# PCB-CMB-5-SKAARDUINO.net
KiCad netlist of a schematic drawn in EAGLE
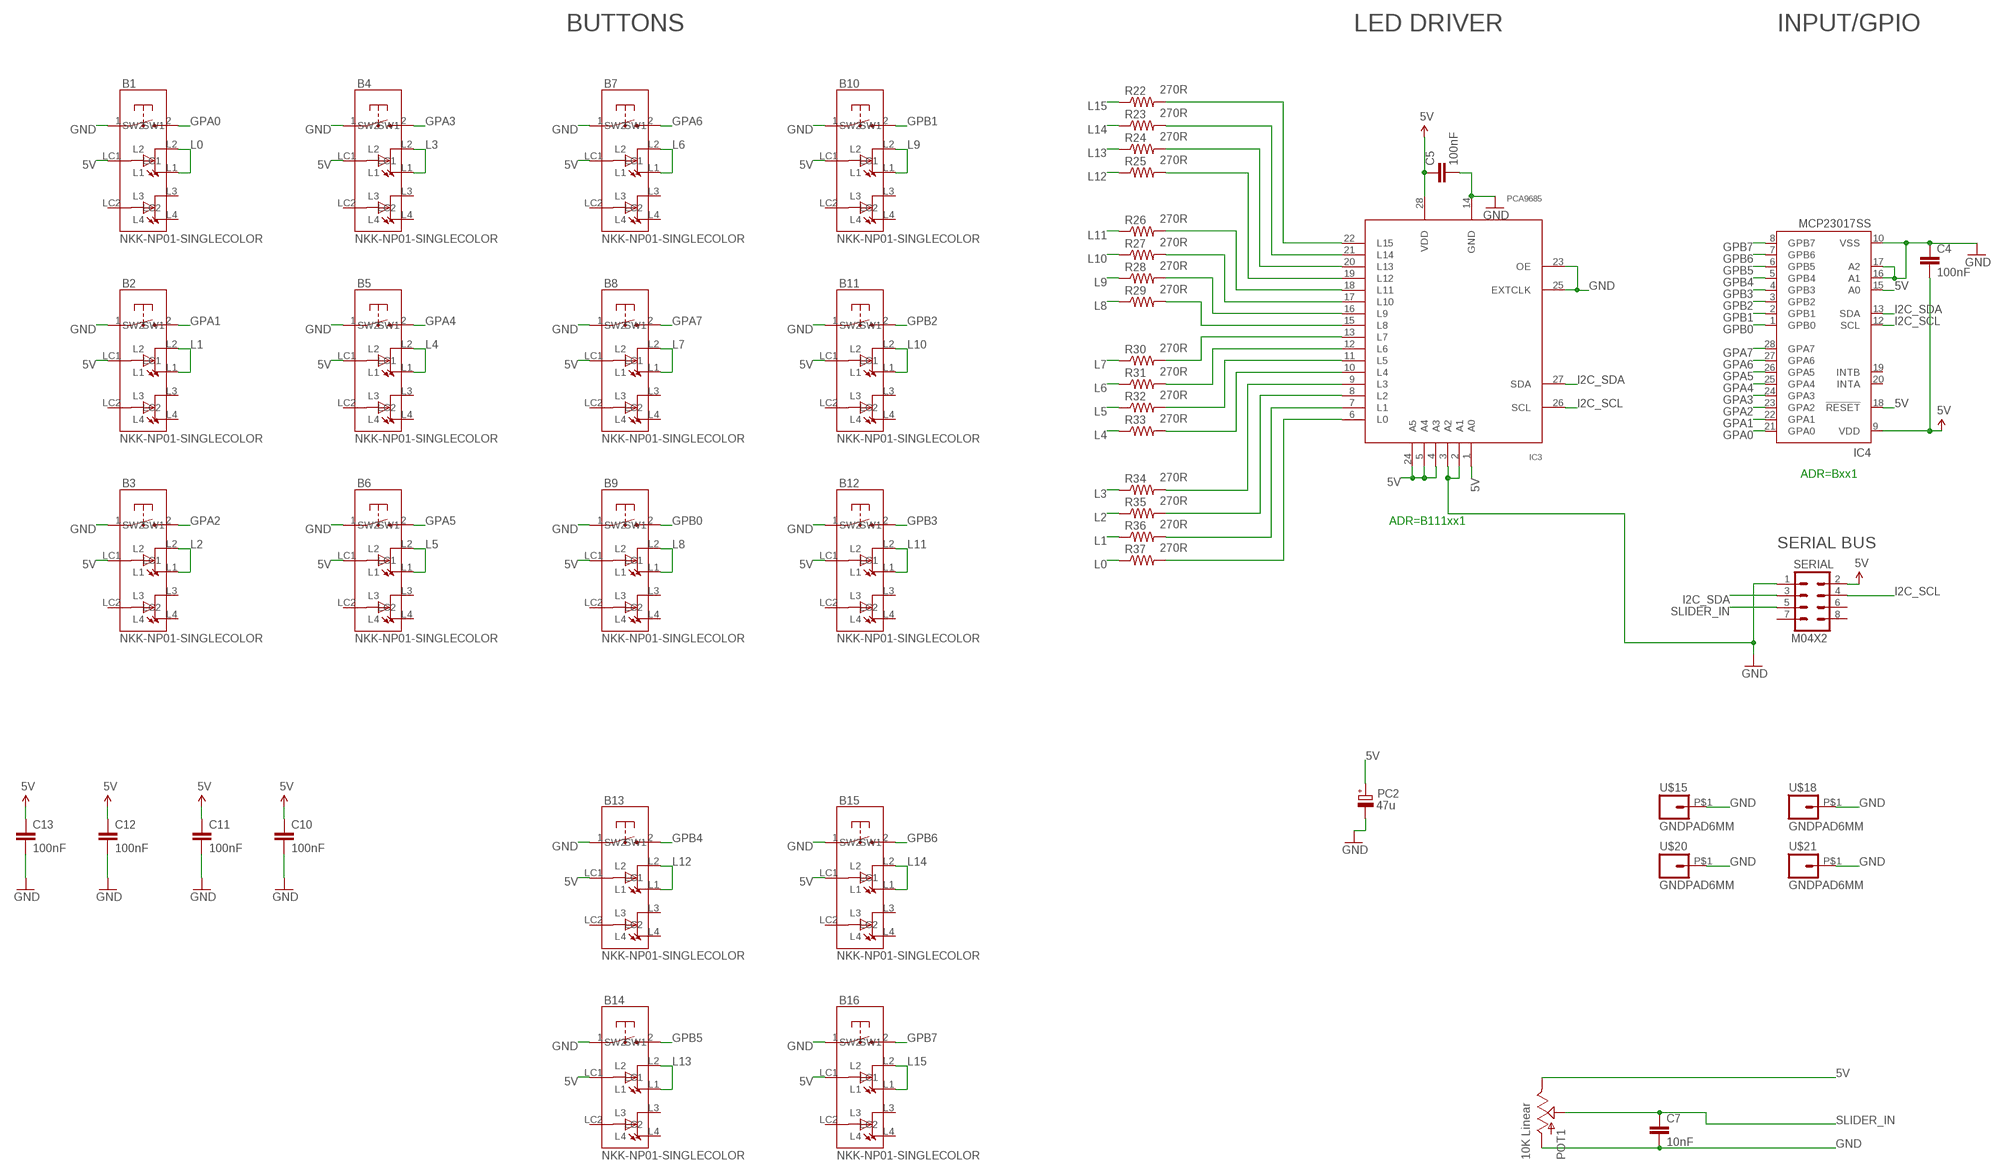
[diagram p0: schematic, sheet 1]

(export (version "E")
  (design (tool "Eeschema 10.0.6"))
  (components
    (comp (ref "B1")
      (value "NKK-NP01-SINGLECOLOR")
      (footprint "eagle-import:NKK-NP01")
      (libsource (lib "eagle-import") (part "NKK-NP01-SINGLECOLOR"))
    )
    (comp (ref "B2")
      (value "NKK-NP01-SINGLECOLOR")
      (footprint "eagle-import:NKK-NP01")
      (libsource (lib "eagle-import") (part "NKK-NP01-SINGLECOLOR"))
    )
    (comp (ref "B3")
      (value "NKK-NP01-SINGLECOLOR")
      (footprint "eagle-import:NKK-NP01")
      (libsource (lib "eagle-import") (part "NKK-NP01-SINGLECOLOR"))
    )
    (comp (ref "B4")
      (value "NKK-NP01-SINGLECOLOR")
      (footprint "eagle-import:NKK-NP01")
      (libsource (lib "eagle-import") (part "NKK-NP01-SINGLECOLOR"))
    )
    (comp (ref "B5")
      (value "NKK-NP01-SINGLECOLOR")
      (footprint "eagle-import:NKK-NP01")
      (libsource (lib "eagle-import") (part "NKK-NP01-SINGLECOLOR"))
    )
    (comp (ref "B6")
      (value "NKK-NP01-SINGLECOLOR")
      (footprint "eagle-import:NKK-NP01")
      (libsource (lib "eagle-import") (part "NKK-NP01-SINGLECOLOR"))
    )
    (comp (ref "B7")
      (value "NKK-NP01-SINGLECOLOR")
      (footprint "eagle-import:NKK-NP01")
      (libsource (lib "eagle-import") (part "NKK-NP01-SINGLECOLOR"))
    )
    (comp (ref "B8")
      (value "NKK-NP01-SINGLECOLOR")
      (footprint "eagle-import:NKK-NP01")
      (libsource (lib "eagle-import") (part "NKK-NP01-SINGLECOLOR"))
    )
    (comp (ref "B9")
      (value "NKK-NP01-SINGLECOLOR")
      (footprint "eagle-import:NKK-NP01")
      (libsource (lib "eagle-import") (part "NKK-NP01-SINGLECOLOR"))
    )
    (comp (ref "B10")
      (value "NKK-NP01-SINGLECOLOR")
      (footprint "eagle-import:NKK-NP01")
      (libsource (lib "eagle-import") (part "NKK-NP01-SINGLECOLOR"))
    )
    (comp (ref "B11")
      (value "NKK-NP01-SINGLECOLOR")
      (footprint "eagle-import:NKK-NP01")
      (libsource (lib "eagle-import") (part "NKK-NP01-SINGLECOLOR"))
    )
    (comp (ref "B12")
      (value "NKK-NP01-SINGLECOLOR")
      (footprint "eagle-import:NKK-NP01")
      (libsource (lib "eagle-import") (part "NKK-NP01-SINGLECOLOR"))
    )
    (comp (ref "B13")
      (value "NKK-NP01-SINGLECOLOR")
      (footprint "eagle-import:NKK-NP01")
      (libsource (lib "eagle-import") (part "NKK-NP01-SINGLECOLOR"))
    )
    (comp (ref "B14")
      (value "NKK-NP01-SINGLECOLOR")
      (footprint "eagle-import:NKK-NP01")
      (libsource (lib "eagle-import") (part "NKK-NP01-SINGLECOLOR"))
    )
    (comp (ref "B15")
      (value "NKK-NP01-SINGLECOLOR")
      (footprint "eagle-import:NKK-NP01")
      (libsource (lib "eagle-import") (part "NKK-NP01-SINGLECOLOR"))
    )
    (comp (ref "B16")
      (value "NKK-NP01-SINGLECOLOR")
      (footprint "eagle-import:NKK-NP01")
      (libsource (lib "eagle-import") (part "NKK-NP01-SINGLECOLOR"))
    )
    (comp (ref "C4")
      (value "100nF")
      (footprint "eagle-import:0603-CAP")
      (libsource (lib "eagle-import") (part "CAP0603-CAP"))
    )
    (comp (ref "C5")
      (value "100nF")
      (footprint "eagle-import:0603-CAP")
      (libsource (lib "eagle-import") (part "CAP0603-CAP"))
    )
    (comp (ref "C7")
      (value "10nF")
      (footprint "eagle-import:0603-CAP")
      (libsource (lib "eagle-import") (part "CAP0603-CAP"))
    )
    (comp (ref "C10")
      (value "100nF")
      (footprint "eagle-import:0603-CAP")
      (libsource (lib "eagle-import") (part "CAP0603-CAP"))
    )
    (comp (ref "C11")
      (value "100nF")
      (footprint "eagle-import:0603-CAP")
      (libsource (lib "eagle-import") (part "CAP0603-CAP"))
    )
    (comp (ref "C12")
      (value "100nF")
      (footprint "eagle-import:0603-CAP")
      (libsource (lib "eagle-import") (part "CAP0603-CAP"))
    )
    (comp (ref "C13")
      (value "100nF")
      (footprint "eagle-import:0603-CAP")
      (libsource (lib "eagle-import") (part "CAP0603-CAP"))
    )
    (comp (ref "IC3")
      (value "PCA9685")
      (footprint "eagle-import:TSSOP28")
      (libsource (lib "eagle-import") (part "PCA9685"))
    )
    (comp (ref "IC4")
      (value "MCP23017SS")
      (footprint "eagle-import:SSOP28")
      (fields
        (field (name "MF") "MICROCHIP")
        (field (name "MPN") "MCP23017-E/SS")
        (field (name "MPN_1") "MCP23017-E/SS")
        (field (name "OC_FARNELL") "1467674")
        (field (name "OC_NEWARK") "31K2960")
      )
      (libsource (lib "eagle-import") (part "MCP23017SS"))
    )
    (comp (ref "PC2")
      (value "47u")
      (footprint "eagle-import:PANASONIC_D")
      (libsource (lib "eagle-import") (part "CPOL-EUD"))
    )
    (comp (ref "POT1")
      (value "10K Linear")
      (footprint "eagle-import:SLIDER20")
      (libsource (lib "eagle-import") (part "SLIDER20"))
    )
    (comp (ref "R22")
      (value "270R")
      (footprint "eagle-import:0603-RES")
      (libsource (lib "eagle-import") (part "RESISTOR0603-RES"))
    )
    (comp (ref "R23")
      (value "270R")
      (footprint "eagle-import:0603-RES")
      (libsource (lib "eagle-import") (part "RESISTOR0603-RES"))
    )
    (comp (ref "R24")
      (value "270R")
      (footprint "eagle-import:0603-RES")
      (libsource (lib "eagle-import") (part "RESISTOR0603-RES"))
    )
    (comp (ref "R25")
      (value "270R")
      (footprint "eagle-import:0603-RES")
      (libsource (lib "eagle-import") (part "RESISTOR0603-RES"))
    )
    (comp (ref "R26")
      (value "270R")
      (footprint "eagle-import:0603-RES")
      (libsource (lib "eagle-import") (part "RESISTOR0603-RES"))
    )
    (comp (ref "R27")
      (value "270R")
      (footprint "eagle-import:0603-RES")
      (libsource (lib "eagle-import") (part "RESISTOR0603-RES"))
    )
    (comp (ref "R28")
      (value "270R")
      (footprint "eagle-import:0603-RES")
      (libsource (lib "eagle-import") (part "RESISTOR0603-RES"))
    )
    (comp (ref "R29")
      (value "270R")
      (footprint "eagle-import:0603-RES")
      (libsource (lib "eagle-import") (part "RESISTOR0603-RES"))
    )
    (comp (ref "R30")
      (value "270R")
      (footprint "eagle-import:0603-RES")
      (libsource (lib "eagle-import") (part "RESISTOR0603-RES"))
    )
    (comp (ref "R31")
      (value "270R")
      (footprint "eagle-import:0603-RES")
      (libsource (lib "eagle-import") (part "RESISTOR0603-RES"))
    )
    (comp (ref "R32")
      (value "270R")
      (footprint "eagle-import:0603-RES")
      (libsource (lib "eagle-import") (part "RESISTOR0603-RES"))
    )
    (comp (ref "R33")
      (value "270R")
      (footprint "eagle-import:0603-RES")
      (libsource (lib "eagle-import") (part "RESISTOR0603-RES"))
    )
    (comp (ref "R34")
      (value "270R")
      (footprint "eagle-import:0603-RES")
      (libsource (lib "eagle-import") (part "RESISTOR0603-RES"))
    )
    (comp (ref "R35")
      (value "270R")
      (footprint "eagle-import:0603-RES")
      (libsource (lib "eagle-import") (part "RESISTOR0603-RES"))
    )
    (comp (ref "R36")
      (value "270R")
      (footprint "eagle-import:0603-RES")
      (libsource (lib "eagle-import") (part "RESISTOR0603-RES"))
    )
    (comp (ref "R37")
      (value "270R")
      (footprint "eagle-import:0603-RES")
      (libsource (lib "eagle-import") (part "RESISTOR0603-RES"))
    )
    (comp (ref "SERIAL")
      (value "M04X2")
      (footprint "eagle-import:2X4")
      (libsource (lib "eagle-import") (part "M04X2"))
    )
    (comp (ref "U$15")
      (value "GNDPAD6MM")
      (footprint "eagle-import:3.2MMPAD6MM")
      (libsource (lib "eagle-import") (part "GNDPAD6MM"))
    )
    (comp (ref "U$18")
      (value "GNDPAD6MM")
      (footprint "eagle-import:3.2MMPAD6MM")
      (libsource (lib "eagle-import") (part "GNDPAD6MM"))
    )
    (comp (ref "U$20")
      (value "GNDPAD6MM")
      (footprint "eagle-import:3.2MMPAD6MM")
      (libsource (lib "eagle-import") (part "GNDPAD6MM"))
    )
    (comp (ref "U$21")
      (value "GNDPAD6MM")
      (footprint "eagle-import:3.2MMPAD6MM")
      (libsource (lib "eagle-import") (part "GNDPAD6MM"))
    )
  )
  (nets
    (net (code "1") (name "5V") (class "Default")
      (node (ref "B1") (pin "LC1") (pinfunction "LC1_LC1") (pintype "bidirectional"))
      (node (ref "B10") (pin "LC1") (pinfunction "LC1_LC1") (pintype "bidirectional"))
      (node (ref "B11") (pin "LC1") (pinfunction "LC1_LC1") (pintype "bidirectional"))
      (node (ref "B12") (pin "LC1") (pinfunction "LC1_LC1") (pintype "bidirectional"))
      (node (ref "B13") (pin "LC1") (pinfunction "LC1_LC1") (pintype "bidirectional"))
      (node (ref "B14") (pin "LC1") (pinfunction "LC1_LC1") (pintype "bidirectional"))
      (node (ref "B15") (pin "LC1") (pinfunction "LC1_LC1") (pintype "bidirectional"))
      (node (ref "B16") (pin "LC1") (pinfunction "LC1_LC1") (pintype "bidirectional"))
      (node (ref "B2") (pin "LC1") (pinfunction "LC1_LC1") (pintype "bidirectional"))
      (node (ref "B3") (pin "LC1") (pinfunction "LC1_LC1") (pintype "bidirectional"))
      (node (ref "B4") (pin "LC1") (pinfunction "LC1_LC1") (pintype "bidirectional"))
      (node (ref "B5") (pin "LC1") (pinfunction "LC1_LC1") (pintype "bidirectional"))
      (node (ref "B6") (pin "LC1") (pinfunction "LC1_LC1") (pintype "bidirectional"))
      (node (ref "B7") (pin "LC1") (pinfunction "LC1_LC1") (pintype "bidirectional"))
      (node (ref "B8") (pin "LC1") (pinfunction "LC1_LC1") (pintype "bidirectional"))
      (node (ref "B9") (pin "LC1") (pinfunction "LC1_LC1") (pintype "bidirectional"))
      (node (ref "C10") (pin "1") (pinfunction "1_1") (pintype "passive"))
      (node (ref "C11") (pin "1") (pinfunction "1_1") (pintype "passive"))
      (node (ref "C12") (pin "1") (pinfunction "1_1") (pintype "passive"))
      (node (ref "C13") (pin "1") (pinfunction "1_1") (pintype "passive"))
      (node (ref "C4") (pin "2") (pinfunction "2_2") (pintype "passive"))
      (node (ref "C5") (pin "1") (pinfunction "1_1") (pintype "passive"))
      (node (ref "IC3") (pin "1") (pinfunction "A0_1") (pintype "input"))
      (node (ref "IC3") (pin "24") (pinfunction "A5_24") (pintype "input"))
      (node (ref "IC3") (pin "28") (pinfunction "VDD_28") (pintype "power_in"))
      (node (ref "IC3") (pin "4") (pinfunction "A3_4") (pintype "input"))
      (node (ref "IC3") (pin "5") (pinfunction "A4_5") (pintype "input"))
      (node (ref "IC4") (pin "15") (pinfunction "A0_15") (pintype "input"))
      (node (ref "IC4") (pin "18") (pinfunction "~{RESET}_18") (pintype "input"))
      (node (ref "IC4") (pin "9") (pinfunction "VDD_9") (pintype "power_in"))
      (node (ref "PC2") (pin "+") (pinfunction "+_+") (pintype "passive"))
      (node (ref "POT1") (pin "1") (pinfunction "E_1") (pintype "passive"))
      (node (ref "SERIAL") (pin "2") (pinfunction "2_2") (pintype "passive"))
    )
    (net (code "2") (name "GND") (class "Default")
      (node (ref "B1") (pin "1") (pinfunction "SW1_1") (pintype "bidirectional"))
      (node (ref "B10") (pin "1") (pinfunction "SW1_1") (pintype "bidirectional"))
      (node (ref "B11") (pin "1") (pinfunction "SW1_1") (pintype "bidirectional"))
      (node (ref "B12") (pin "1") (pinfunction "SW1_1") (pintype "bidirectional"))
      (node (ref "B13") (pin "1") (pinfunction "SW1_1") (pintype "bidirectional"))
      (node (ref "B14") (pin "1") (pinfunction "SW1_1") (pintype "bidirectional"))
      (node (ref "B15") (pin "1") (pinfunction "SW1_1") (pintype "bidirectional"))
      (node (ref "B16") (pin "1") (pinfunction "SW1_1") (pintype "bidirectional"))
      (node (ref "B2") (pin "1") (pinfunction "SW1_1") (pintype "bidirectional"))
      (node (ref "B3") (pin "1") (pinfunction "SW1_1") (pintype "bidirectional"))
      (node (ref "B4") (pin "1") (pinfunction "SW1_1") (pintype "bidirectional"))
      (node (ref "B5") (pin "1") (pinfunction "SW1_1") (pintype "bidirectional"))
      (node (ref "B6") (pin "1") (pinfunction "SW1_1") (pintype "bidirectional"))
      (node (ref "B7") (pin "1") (pinfunction "SW1_1") (pintype "bidirectional"))
      (node (ref "B8") (pin "1") (pinfunction "SW1_1") (pintype "bidirectional"))
      (node (ref "B9") (pin "1") (pinfunction "SW1_1") (pintype "bidirectional"))
      (node (ref "C10") (pin "2") (pinfunction "2_2") (pintype "passive"))
      (node (ref "C11") (pin "2") (pinfunction "2_2") (pintype "passive"))
      (node (ref "C12") (pin "2") (pinfunction "2_2") (pintype "passive"))
      (node (ref "C13") (pin "2") (pinfunction "2_2") (pintype "passive"))
      (node (ref "C4") (pin "1") (pinfunction "1_1") (pintype "passive"))
      (node (ref "C5") (pin "2") (pinfunction "2_2") (pintype "passive"))
      (node (ref "C7") (pin "2") (pinfunction "2_2") (pintype "passive"))
      (node (ref "IC3") (pin "14") (pinfunction "GND_14") (pintype "power_in"))
      (node (ref "IC3") (pin "2") (pinfunction "A1_2") (pintype "input"))
      (node (ref "IC3") (pin "23") (pinfunction "OE_23") (pintype "input"))
      (node (ref "IC3") (pin "25") (pinfunction "EXTCLK_25") (pintype "input"))
      (node (ref "IC3") (pin "3") (pinfunction "A2_3") (pintype "input"))
      (node (ref "IC4") (pin "10") (pinfunction "VSS_10") (pintype "power_in"))
      (node (ref "IC4") (pin "16") (pinfunction "A1_16") (pintype "input"))
      (node (ref "IC4") (pin "17") (pinfunction "A2_17") (pintype "input"))
      (node (ref "PC2") (pin "-") (pinfunction "-_-") (pintype "passive"))
      (node (ref "POT1") (pin "3") (pinfunction "A_3") (pintype "passive"))
      (node (ref "SERIAL") (pin "1") (pinfunction "1_1") (pintype "passive"))
      (node (ref "U$15") (pin "P$1") (pinfunction "1_P$1") (pintype "passive"))
      (node (ref "U$18") (pin "P$1") (pinfunction "1_P$1") (pintype "passive"))
      (node (ref "U$20") (pin "P$1") (pinfunction "1_P$1") (pintype "passive"))
      (node (ref "U$21") (pin "P$1") (pinfunction "1_P$1") (pintype "passive"))
    )
    (net (code "3") (name "GPA0") (class "Default")
      (node (ref "B1") (pin "2") (pinfunction "SW2_2") (pintype "bidirectional"))
      (node (ref "IC4") (pin "21") (pinfunction "GPA0_21") (pintype "bidirectional"))
    )
    (net (code "4") (name "GPA1") (class "Default")
      (node (ref "B2") (pin "2") (pinfunction "SW2_2") (pintype "bidirectional"))
      (node (ref "IC4") (pin "22") (pinfunction "GPA1_22") (pintype "bidirectional"))
    )
    (net (code "5") (name "GPA2") (class "Default")
      (node (ref "B3") (pin "2") (pinfunction "SW2_2") (pintype "bidirectional"))
      (node (ref "IC4") (pin "23") (pinfunction "GPA2_23") (pintype "bidirectional"))
    )
    (net (code "6") (name "GPA3") (class "Default")
      (node (ref "B4") (pin "2") (pinfunction "SW2_2") (pintype "bidirectional"))
      (node (ref "IC4") (pin "24") (pinfunction "GPA3_24") (pintype "bidirectional"))
    )
    (net (code "7") (name "GPA4") (class "Default")
      (node (ref "B5") (pin "2") (pinfunction "SW2_2") (pintype "bidirectional"))
      (node (ref "IC4") (pin "25") (pinfunction "GPA4_25") (pintype "bidirectional"))
    )
    (net (code "8") (name "GPA5") (class "Default")
      (node (ref "B6") (pin "2") (pinfunction "SW2_2") (pintype "bidirectional"))
      (node (ref "IC4") (pin "26") (pinfunction "GPA5_26") (pintype "bidirectional"))
    )
    (net (code "9") (name "GPA6") (class "Default")
      (node (ref "B7") (pin "2") (pinfunction "SW2_2") (pintype "bidirectional"))
      (node (ref "IC4") (pin "27") (pinfunction "GPA6_27") (pintype "bidirectional"))
    )
    (net (code "10") (name "GPA7") (class "Default")
      (node (ref "B8") (pin "2") (pinfunction "SW2_2") (pintype "bidirectional"))
      (node (ref "IC4") (pin "28") (pinfunction "GPA7_28") (pintype "bidirectional"))
    )
    (net (code "11") (name "GPB0") (class "Default")
      (node (ref "B9") (pin "2") (pinfunction "SW2_2") (pintype "bidirectional"))
      (node (ref "IC4") (pin "1") (pinfunction "GPB0_1") (pintype "bidirectional"))
    )
    (net (code "12") (name "GPB1") (class "Default")
      (node (ref "B10") (pin "2") (pinfunction "SW2_2") (pintype "bidirectional"))
      (node (ref "IC4") (pin "2") (pinfunction "GPB1_2") (pintype "bidirectional"))
    )
    (net (code "13") (name "GPB2") (class "Default")
      (node (ref "B11") (pin "2") (pinfunction "SW2_2") (pintype "bidirectional"))
      (node (ref "IC4") (pin "3") (pinfunction "GPB2_3") (pintype "bidirectional"))
    )
    (net (code "14") (name "GPB3") (class "Default")
      (node (ref "B12") (pin "2") (pinfunction "SW2_2") (pintype "bidirectional"))
      (node (ref "IC4") (pin "4") (pinfunction "GPB3_4") (pintype "bidirectional"))
    )
    (net (code "15") (name "GPB4") (class "Default")
      (node (ref "B13") (pin "2") (pinfunction "SW2_2") (pintype "bidirectional"))
      (node (ref "IC4") (pin "5") (pinfunction "GPB4_5") (pintype "bidirectional"))
    )
    (net (code "16") (name "GPB5") (class "Default")
      (node (ref "B14") (pin "2") (pinfunction "SW2_2") (pintype "bidirectional"))
      (node (ref "IC4") (pin "6") (pinfunction "GPB5_6") (pintype "bidirectional"))
    )
    (net (code "17") (name "GPB6") (class "Default")
      (node (ref "B15") (pin "2") (pinfunction "SW2_2") (pintype "bidirectional"))
      (node (ref "IC4") (pin "7") (pinfunction "GPB6_7") (pintype "bidirectional"))
    )
    (net (code "18") (name "GPB7") (class "Default")
      (node (ref "B16") (pin "2") (pinfunction "SW2_2") (pintype "bidirectional"))
      (node (ref "IC4") (pin "8") (pinfunction "GPB7_8") (pintype "bidirectional"))
    )
    (net (code "19") (name "I2C_SCL") (class "Default")
      (node (ref "IC3") (pin "26") (pinfunction "SCL_26") (pintype "input"))
      (node (ref "IC4") (pin "12") (pinfunction "SCL_12") (pintype "input"))
      (node (ref "SERIAL") (pin "4") (pinfunction "4_4") (pintype "passive"))
    )
    (net (code "20") (name "I2C_SDA") (class "Default")
      (node (ref "IC3") (pin "27") (pinfunction "SDA_27") (pintype "input"))
      (node (ref "IC4") (pin "13") (pinfunction "SDA_13") (pintype "bidirectional"))
      (node (ref "SERIAL") (pin "3") (pinfunction "3_3") (pintype "passive"))
    )
    (net (code "21") (name "L0") (class "Default")
      (node (ref "B1") (pin "L1") (pinfunction "L1_L1") (pintype "bidirectional"))
      (node (ref "B1") (pin "L2") (pinfunction "L2_L2") (pintype "bidirectional"))
      (node (ref "R37") (pin "1") (pinfunction "1_1") (pintype "passive"))
    )
    (net (code "22") (name "L1") (class "Default")
      (node (ref "B2") (pin "L1") (pinfunction "L1_L1") (pintype "bidirectional"))
      (node (ref "B2") (pin "L2") (pinfunction "L2_L2") (pintype "bidirectional"))
      (node (ref "R36") (pin "1") (pinfunction "1_1") (pintype "passive"))
    )
    (net (code "23") (name "L2") (class "Default")
      (node (ref "B3") (pin "L1") (pinfunction "L1_L1") (pintype "bidirectional"))
      (node (ref "B3") (pin "L2") (pinfunction "L2_L2") (pintype "bidirectional"))
      (node (ref "R35") (pin "1") (pinfunction "1_1") (pintype "passive"))
    )
    (net (code "24") (name "L3") (class "Default")
      (node (ref "B4") (pin "L1") (pinfunction "L1_L1") (pintype "bidirectional"))
      (node (ref "B4") (pin "L2") (pinfunction "L2_L2") (pintype "bidirectional"))
      (node (ref "R34") (pin "1") (pinfunction "1_1") (pintype "passive"))
    )
    (net (code "25") (name "L4") (class "Default")
      (node (ref "B5") (pin "L1") (pinfunction "L1_L1") (pintype "bidirectional"))
      (node (ref "B5") (pin "L2") (pinfunction "L2_L2") (pintype "bidirectional"))
      (node (ref "R33") (pin "1") (pinfunction "1_1") (pintype "passive"))
    )
    (net (code "26") (name "L5") (class "Default")
      (node (ref "B6") (pin "L1") (pinfunction "L1_L1") (pintype "bidirectional"))
      (node (ref "B6") (pin "L2") (pinfunction "L2_L2") (pintype "bidirectional"))
      (node (ref "R32") (pin "1") (pinfunction "1_1") (pintype "passive"))
    )
    (net (code "27") (name "L6") (class "Default")
      (node (ref "B7") (pin "L1") (pinfunction "L1_L1") (pintype "bidirectional"))
      (node (ref "B7") (pin "L2") (pinfunction "L2_L2") (pintype "bidirectional"))
      (node (ref "R31") (pin "1") (pinfunction "1_1") (pintype "passive"))
    )
    (net (code "28") (name "L7") (class "Default")
      (node (ref "B8") (pin "L1") (pinfunction "L1_L1") (pintype "bidirectional"))
      (node (ref "B8") (pin "L2") (pinfunction "L2_L2") (pintype "bidirectional"))
      (node (ref "R30") (pin "1") (pinfunction "1_1") (pintype "passive"))
    )
    (net (code "29") (name "L8") (class "Default")
      (node (ref "B9") (pin "L1") (pinfunction "L1_L1") (pintype "bidirectional"))
      (node (ref "B9") (pin "L2") (pinfunction "L2_L2") (pintype "bidirectional"))
      (node (ref "R29") (pin "1") (pinfunction "1_1") (pintype "passive"))
    )
    (net (code "30") (name "L9") (class "Default")
      (node (ref "B10") (pin "L1") (pinfunction "L1_L1") (pintype "bidirectional"))
      (node (ref "B10") (pin "L2") (pinfunction "L2_L2") (pintype "bidirectional"))
      (node (ref "R28") (pin "1") (pinfunction "1_1") (pintype "passive"))
    )
    (net (code "31") (name "L10") (class "Default")
      (node (ref "B11") (pin "L1") (pinfunction "L1_L1") (pintype "bidirectional"))
      (node (ref "B11") (pin "L2") (pinfunction "L2_L2") (pintype "bidirectional"))
      (node (ref "R27") (pin "1") (pinfunction "1_1") (pintype "passive"))
    )
    (net (code "32") (name "L11") (class "Default")
      (node (ref "B12") (pin "L1") (pinfunction "L1_L1") (pintype "bidirectional"))
      (node (ref "B12") (pin "L2") (pinfunction "L2_L2") (pintype "bidirectional"))
      (node (ref "R26") (pin "1") (pinfunction "1_1") (pintype "passive"))
    )
    (net (code "33") (name "L12") (class "Default")
      (node (ref "B13") (pin "L1") (pinfunction "L1_L1") (pintype "bidirectional"))
      (node (ref "B13") (pin "L2") (pinfunction "L2_L2") (pintype "bidirectional"))
      (node (ref "R25") (pin "1") (pinfunction "1_1") (pintype "passive"))
    )
    (net (code "34") (name "L13") (class "Default")
      (node (ref "B14") (pin "L1") (pinfunction "L1_L1") (pintype "bidirectional"))
      (node (ref "B14") (pin "L2") (pinfunction "L2_L2") (pintype "bidirectional"))
      (node (ref "R24") (pin "1") (pinfunction "1_1") (pintype "passive"))
    )
    (net (code "35") (name "L14") (class "Default")
      (node (ref "B15") (pin "L1") (pinfunction "L1_L1") (pintype "bidirectional"))
      (node (ref "B15") (pin "L2") (pinfunction "L2_L2") (pintype "bidirectional"))
      (node (ref "R23") (pin "1") (pinfunction "1_1") (pintype "passive"))
    )
    (net (code "36") (name "L15") (class "Default")
      (node (ref "B16") (pin "L1") (pinfunction "L1_L1") (pintype "bidirectional"))
      (node (ref "B16") (pin "L2") (pinfunction "L2_L2") (pintype "bidirectional"))
      (node (ref "R22") (pin "1") (pinfunction "1_1") (pintype "passive"))
    )
    (net (code "37") (name "Net-(IC3-L0)") (class "Default")
      (node (ref "IC3") (pin "6") (pinfunction "L0_6") (pintype "output"))
      (node (ref "R37") (pin "2") (pinfunction "2_2") (pintype "passive"))
    )
    (net (code "38") (name "Net-(IC3-L1)") (class "Default")
      (node (ref "IC3") (pin "7") (pinfunction "L1_7") (pintype "output"))
      (node (ref "R36") (pin "2") (pinfunction "2_2") (pintype "passive"))
    )
    (net (code "39") (name "Net-(IC3-L2)") (class "Default")
      (node (ref "IC3") (pin "8") (pinfunction "L2_8") (pintype "output"))
      (node (ref "R35") (pin "2") (pinfunction "2_2") (pintype "passive"))
    )
    (net (code "40") (name "Net-(IC3-L3)") (class "Default")
      (node (ref "IC3") (pin "9") (pinfunction "L3_9") (pintype "output"))
      (node (ref "R34") (pin "2") (pinfunction "2_2") (pintype "passive"))
    )
    (net (code "41") (name "Net-(IC3-L4)") (class "Default")
      (node (ref "IC3") (pin "10") (pinfunction "L4_10") (pintype "output"))
      (node (ref "R33") (pin "2") (pinfunction "2_2") (pintype "passive"))
    )
    (net (code "42") (name "Net-(IC3-L5)") (class "Default")
      (node (ref "IC3") (pin "11") (pinfunction "L5_11") (pintype "output"))
      (node (ref "R32") (pin "2") (pinfunction "2_2") (pintype "passive"))
    )
    (net (code "43") (name "Net-(IC3-L6)") (class "Default")
      (node (ref "IC3") (pin "12") (pinfunction "L6_12") (pintype "output"))
      (node (ref "R31") (pin "2") (pinfunction "2_2") (pintype "passive"))
    )
    (net (code "44") (name "Net-(IC3-L7)") (class "Default")
      (node (ref "IC3") (pin "13") (pinfunction "L7_13") (pintype "output"))
      (node (ref "R30") (pin "2") (pinfunction "2_2") (pintype "passive"))
    )
    (net (code "45") (name "Net-(IC3-L8)") (class "Default")
      (node (ref "IC3") (pin "15") (pinfunction "L8_15") (pintype "output"))
      (node (ref "R29") (pin "2") (pinfunction "2_2") (pintype "passive"))
    )
    (net (code "46") (name "Net-(IC3-L9)") (class "Default")
      (node (ref "IC3") (pin "16") (pinfunction "L9_16") (pintype "output"))
      (node (ref "R28") (pin "2") (pinfunction "2_2") (pintype "passive"))
    )
    (net (code "47") (name "Net-(IC3-L10)") (class "Default")
      (node (ref "IC3") (pin "17") (pinfunction "L10_17") (pintype "output"))
      (node (ref "R27") (pin "2") (pinfunction "2_2") (pintype "passive"))
    )
    (net (code "48") (name "Net-(IC3-L11)") (class "Default")
      (node (ref "IC3") (pin "18") (pinfunction "L11_18") (pintype "output"))
      (node (ref "R26") (pin "2") (pinfunction "2_2") (pintype "passive"))
    )
    (net (code "49") (name "Net-(IC3-L12)") (class "Default")
      (node (ref "IC3") (pin "19") (pinfunction "L12_19") (pintype "output"))
      (node (ref "R25") (pin "2") (pinfunction "2_2") (pintype "passive"))
    )
    (net (code "50") (name "Net-(IC3-L13)") (class "Default")
      (node (ref "IC3") (pin "20") (pinfunction "L13_20") (pintype "output"))
      (node (ref "R24") (pin "2") (pinfunction "2_2") (pintype "passive"))
    )
    (net (code "51") (name "Net-(IC3-L14)") (class "Default")
      (node (ref "IC3") (pin "21") (pinfunction "L14_21") (pintype "output"))
      (node (ref "R23") (pin "2") (pinfunction "2_2") (pintype "passive"))
    )
    (net (code "52") (name "Net-(IC3-L15)") (class "Default")
      (node (ref "IC3") (pin "22") (pinfunction "L15_22") (pintype "output"))
      (node (ref "R22") (pin "2") (pinfunction "2_2") (pintype "passive"))
    )
    (net (code "53") (name "SLIDER_IN") (class "Default")
      (node (ref "C7") (pin "1") (pinfunction "1_1") (pintype "passive"))
      (node (ref "POT1") (pin "2A") (pinfunction "S_2A") (pintype "passive"))
      (node (ref "SERIAL") (pin "5") (pinfunction "5_5") (pintype "passive"))
    )
    (net (code "54") (name "unconnected-(B1-PadL3)") (class "Default")
      (node (ref "B1") (pin "L3") (pinfunction "L3_L3") (pintype "bidirectional"))
    )
    (net (code "55") (name "unconnected-(B1-PadL4)") (class "Default")
      (node (ref "B1") (pin "L4") (pinfunction "L4_L4") (pintype "bidirectional"))
    )
    (net (code "56") (name "unconnected-(B1-PadLC2)") (class "Default")
      (node (ref "B1") (pin "LC2") (pinfunction "LC2_LC2") (pintype "bidirectional"))
    )
    (net (code "57") (name "unconnected-(B2-PadL3)") (class "Default")
      (node (ref "B2") (pin "L3") (pinfunction "L3_L3") (pintype "bidirectional"))
    )
    (net (code "58") (name "unconnected-(B2-PadL4)") (class "Default")
      (node (ref "B2") (pin "L4") (pinfunction "L4_L4") (pintype "bidirectional"))
    )
    (net (code "59") (name "unconnected-(B2-PadLC2)") (class "Default")
      (node (ref "B2") (pin "LC2") (pinfunction "LC2_LC2") (pintype "bidirectional"))
    )
    (net (code "60") (name "unconnected-(B3-PadL3)") (class "Default")
      (node (ref "B3") (pin "L3") (pinfunction "L3_L3") (pintype "bidirectional"))
    )
    (net (code "61") (name "unconnected-(B3-PadL4)") (class "Default")
      (node (ref "B3") (pin "L4") (pinfunction "L4_L4") (pintype "bidirectional"))
    )
    (net (code "62") (name "unconnected-(B3-PadLC2)") (class "Default")
      (node (ref "B3") (pin "LC2") (pinfunction "LC2_LC2") (pintype "bidirectional"))
    )
    (net (code "63") (name "unconnected-(B4-PadL3)") (class "Default")
      (node (ref "B4") (pin "L3") (pinfunction "L3_L3") (pintype "bidirectional"))
    )
    (net (code "64") (name "unconnected-(B4-PadL4)") (class "Default")
      (node (ref "B4") (pin "L4") (pinfunction "L4_L4") (pintype "bidirectional"))
    )
    (net (code "65") (name "unconnected-(B4-PadLC2)") (class "Default")
      (node (ref "B4") (pin "LC2") (pinfunction "LC2_LC2") (pintype "bidirectional"))
    )
    (net (code "66") (name "unconnected-(B5-PadL3)") (class "Default")
      (node (ref "B5") (pin "L3") (pinfunction "L3_L3") (pintype "bidirectional"))
    )
    (net (code "67") (name "unconnected-(B5-PadL4)") (class "Default")
      (node (ref "B5") (pin "L4") (pinfunction "L4_L4") (pintype "bidirectional"))
    )
    (net (code "68") (name "unconnected-(B5-PadLC2)") (class "Default")
      (node (ref "B5") (pin "LC2") (pinfunction "LC2_LC2") (pintype "bidirectional"))
    )
    (net (code "69") (name "unconnected-(B6-PadL3)") (class "Default")
      (node (ref "B6") (pin "L3") (pinfunction "L3_L3") (pintype "bidirectional"))
    )
    (net (code "70") (name "unconnected-(B6-PadL4)") (class "Default")
      (node (ref "B6") (pin "L4") (pinfunction "L4_L4") (pintype "bidirectional"))
    )
    (net (code "71") (name "unconnected-(B6-PadLC2)") (class "Default")
      (node (ref "B6") (pin "LC2") (pinfunction "LC2_LC2") (pintype "bidirectional"))
    )
    (net (code "72") (name "unconnected-(B7-PadL3)") (class "Default")
      (node (ref "B7") (pin "L3") (pinfunction "L3_L3") (pintype "bidirectional"))
    )
    (net (code "73") (name "unconnected-(B7-PadL4)") (class "Default")
      (node (ref "B7") (pin "L4") (pinfunction "L4_L4") (pintype "bidirectional"))
    )
    (net (code "74") (name "unconnected-(B7-PadLC2)") (class "Default")
      (node (ref "B7") (pin "LC2") (pinfunction "LC2_LC2") (pintype "bidirectional"))
    )
    (net (code "75") (name "unconnected-(B8-PadL3)") (class "Default")
      (node (ref "B8") (pin "L3") (pinfunction "L3_L3") (pintype "bidirectional"))
    )
    (net (code "76") (name "unconnected-(B8-PadL4)") (class "Default")
      (node (ref "B8") (pin "L4") (pinfunction "L4_L4") (pintype "bidirectional"))
    )
    (net (code "77") (name "unconnected-(B8-PadLC2)") (class "Default")
      (node (ref "B8") (pin "LC2") (pinfunction "LC2_LC2") (pintype "bidirectional"))
    )
    (net (code "78") (name "unconnected-(B9-PadL3)") (class "Default")
      (node (ref "B9") (pin "L3") (pinfunction "L3_L3") (pintype "bidirectional"))
    )
    (net (code "79") (name "unconnected-(B9-PadL4)") (class "Default")
      (node (ref "B9") (pin "L4") (pinfunction "L4_L4") (pintype "bidirectional"))
    )
    (net (code "80") (name "unconnected-(B9-PadLC2)") (class "Default")
      (node (ref "B9") (pin "LC2") (pinfunction "LC2_LC2") (pintype "bidirectional"))
    )
    (net (code "81") (name "unconnected-(B10-PadL3)") (class "Default")
      (node (ref "B10") (pin "L3") (pinfunction "L3_L3") (pintype "bidirectional"))
    )
    (net (code "82") (name "unconnected-(B10-PadL4)") (class "Default")
      (node (ref "B10") (pin "L4") (pinfunction "L4_L4") (pintype "bidirectional"))
    )
    (net (code "83") (name "unconnected-(B10-PadLC2)") (class "Default")
      (node (ref "B10") (pin "LC2") (pinfunction "LC2_LC2") (pintype "bidirectional"))
    )
    (net (code "84") (name "unconnected-(B11-PadL3)") (class "Default")
      (node (ref "B11") (pin "L3") (pinfunction "L3_L3") (pintype "bidirectional"))
    )
    (net (code "85") (name "unconnected-(B11-PadL4)") (class "Default")
      (node (ref "B11") (pin "L4") (pinfunction "L4_L4") (pintype "bidirectional"))
    )
    (net (code "86") (name "unconnected-(B11-PadLC2)") (class "Default")
      (node (ref "B11") (pin "LC2") (pinfunction "LC2_LC2") (pintype "bidirectional"))
    )
    (net (code "87") (name "unconnected-(B12-PadL3)") (class "Default")
      (node (ref "B12") (pin "L3") (pinfunction "L3_L3") (pintype "bidirectional"))
    )
    (net (code "88") (name "unconnected-(B12-PadL4)") (class "Default")
      (node (ref "B12") (pin "L4") (pinfunction "L4_L4") (pintype "bidirectional"))
    )
    (net (code "89") (name "unconnected-(B12-PadLC2)") (class "Default")
      (node (ref "B12") (pin "LC2") (pinfunction "LC2_LC2") (pintype "bidirectional"))
    )
    (net (code "90") (name "unconnected-(B13-PadL3)") (class "Default")
      (node (ref "B13") (pin "L3") (pinfunction "L3_L3") (pintype "bidirectional"))
    )
    (net (code "91") (name "unconnected-(B13-PadL4)") (class "Default")
      (node (ref "B13") (pin "L4") (pinfunction "L4_L4") (pintype "bidirectional"))
    )
    (net (code "92") (name "unconnected-(B13-PadLC2)") (class "Default")
      (node (ref "B13") (pin "LC2") (pinfunction "LC2_LC2") (pintype "bidirectional"))
    )
    (net (code "93") (name "unconnected-(B14-PadL3)") (class "Default")
      (node (ref "B14") (pin "L3") (pinfunction "L3_L3") (pintype "bidirectional"))
    )
    (net (code "94") (name "unconnected-(B14-PadL4)") (class "Default")
      (node (ref "B14") (pin "L4") (pinfunction "L4_L4") (pintype "bidirectional"))
    )
    (net (code "95") (name "unconnected-(B14-PadLC2)") (class "Default")
      (node (ref "B14") (pin "LC2") (pinfunction "LC2_LC2") (pintype "bidirectional"))
    )
    (net (code "96") (name "unconnected-(B15-PadL3)") (class "Default")
      (node (ref "B15") (pin "L3") (pinfunction "L3_L3") (pintype "bidirectional"))
    )
    (net (code "97") (name "unconnected-(B15-PadL4)") (class "Default")
      (node (ref "B15") (pin "L4") (pinfunction "L4_L4") (pintype "bidirectional"))
    )
    (net (code "98") (name "unconnected-(B15-PadLC2)") (class "Default")
      (node (ref "B15") (pin "LC2") (pinfunction "LC2_LC2") (pintype "bidirectional"))
    )
    (net (code "99") (name "unconnected-(B16-PadL3)") (class "Default")
      (node (ref "B16") (pin "L3") (pinfunction "L3_L3") (pintype "bidirectional"))
    )
    (net (code "100") (name "unconnected-(B16-PadL4)") (class "Default")
      (node (ref "B16") (pin "L4") (pinfunction "L4_L4") (pintype "bidirectional"))
    )
    (net (code "101") (name "unconnected-(B16-PadLC2)") (class "Default")
      (node (ref "B16") (pin "LC2") (pinfunction "LC2_LC2") (pintype "bidirectional"))
    )
    (net (code "102") (name "unconnected-(IC4-INTA-Pad20)") (class "Default")
      (node (ref "IC4") (pin "20") (pinfunction "INTA_20") (pintype "output"))
    )
    (net (code "103") (name "unconnected-(IC4-INTB-Pad19)") (class "Default")
      (node (ref "IC4") (pin "19") (pinfunction "INTB_19") (pintype "output"))
    )
    (net (code "104") (name "unconnected-(SERIAL-Pad6)") (class "Default")
      (node (ref "SERIAL") (pin "6") (pinfunction "6_6") (pintype "passive"))
    )
    (net (code "105") (name "unconnected-(SERIAL-Pad7)") (class "Default")
      (node (ref "SERIAL") (pin "7") (pinfunction "7_7") (pintype "passive"))
    )
    (net (code "106") (name "unconnected-(SERIAL-Pad8)") (class "Default")
      (node (ref "SERIAL") (pin "8") (pinfunction "8_8") (pintype "passive"))
    )
  )
)
